# AuxHalfH.net
KiCad netlist of a schematic drawn in Altium Designer
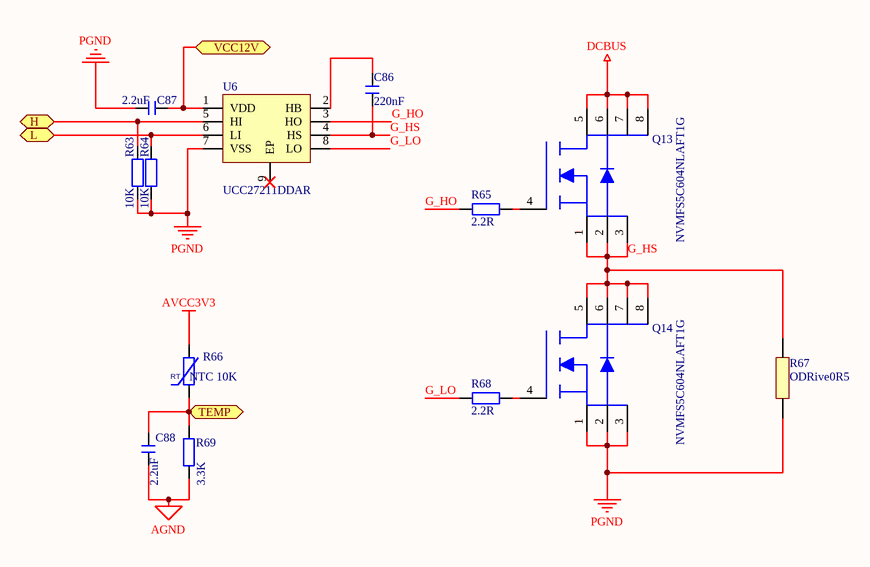
[diagram p0: AuxHalfH.SchDoc]

(export (version "E")
  (design (tool "Eeschema 10.0.6"))
  (components
    (comp (ref "C86")
      (value "220nF")
      (footprint "C 0805_L")
      (description "贴片电容")
      (libsource (lib "0.1 - 电阻-电容-电感") (part "C"))
    )
    (comp (ref "C87")
      (value "2.2uF")
      (footprint "C 0603_L")
      (description "贴片电容")
      (libsource (lib "0.1 - 电阻-电容-电感") (part "C"))
    )
    (comp (ref "C88")
      (value "2.2uF")
      (footprint "C 0603_L")
      (description "贴片电容")
      (libsource (lib "0.1 - 电阻-电容-电感") (part "C"))
    )
    (comp (ref "Q13")
      (value "NVMFS5C604NLAFT1G")
      (footprint "PG-TDSON-8_L5.0-W6.0-P1.27-LS6.2-BL-EP")
      (libsource (lib "mx_pcb_library") (part "BSC037N08NS5ATMA1"))
    )
    (comp (ref "Q14")
      (value "NVMFS5C604NLAFT1G")
      (footprint "PG-TDSON-8_L5.0-W6.0-P1.27-LS6.2-BL-EP")
      (libsource (lib "mx_pcb_library") (part "BSC037N08NS5ATMA1"))
    )
    (comp (ref "R63")
      (value "10K")
      (footprint "R 0603_L")
      (description "贴片电阻")
      (libsource (lib "0.1 - 电阻-电容-电感") (part "R"))
    )
    (comp (ref "R64")
      (value "10K")
      (footprint "R 0603_L")
      (description "贴片电阻")
      (libsource (lib "0.1 - 电阻-电容-电感") (part "R"))
    )
    (comp (ref "R65")
      (value "2.2R")
      (footprint "R 0603_L")
      (description "贴片电阻")
      (libsource (lib "0.1 - 电阻-电容-电感") (part "R"))
    )
    (comp (ref "R66")
      (value "NTC 10K")
      (footprint "R 0805-HP_L")
      (description "热敏电阻")
      (libsource (lib "0.1 - 电阻-电容-电感") (part "RT"))
    )
    (comp (ref "R67")
      (value "ODRive0R5")
      (footprint "ODrive_0R5")
      (libsource (lib "mx_pcb_library") (part "ODRive0R5"))
    )
    (comp (ref "R68")
      (value "2.2R")
      (footprint "R 0603_L")
      (description "贴片电阻")
      (libsource (lib "0.1 - 电阻-电容-电感") (part "R"))
    )
    (comp (ref "R69")
      (value "3.3K")
      (footprint "R 0805_L")
      (description "贴片电阻")
      (libsource (lib "0.1 - 电阻-电容-电感") (part "R"))
    )
    (comp (ref "U6")
      (value "UCC27211DDAR")
      (footprint "SO-8_EP")
      (libsource (lib "mx_pcb_library") (part "UCC27211DDAR"))
    )
  )
  (nets
    (net (code "1") (name "/G_HO") (class "Default")
      (node (ref "R65") (pin "1") (pinfunction "1_1") (pintype "passive"))
      (node (ref "U6") (pin "3") (pinfunction "HO_3") (pintype "passive"))
    )
    (net (code "2") (name "/G_HS") (class "Default")
      (node (ref "C86") (pin "1") (pinfunction "1_1") (pintype "passive"))
      (node (ref "Q13") (pin "1") (pinfunction "1_1") (pintype "passive"))
      (node (ref "Q13") (pin "2") (pinfunction "2_2") (pintype "passive"))
      (node (ref "Q13") (pin "3") (pinfunction "3_3") (pintype "passive"))
      (node (ref "Q14") (pin "5") (pinfunction "5_5") (pintype "passive"))
      (node (ref "Q14") (pin "6") (pinfunction "6_6") (pintype "passive"))
      (node (ref "Q14") (pin "7") (pinfunction "7_7") (pintype "passive"))
      (node (ref "Q14") (pin "8") (pinfunction "8_8") (pintype "passive"))
      (node (ref "R67") (pin "2") (pinfunction "2_2") (pintype "passive"))
      (node (ref "U6") (pin "4") (pinfunction "HS_4") (pintype "passive"))
    )
    (net (code "3") (name "/G_LO") (class "Default")
      (node (ref "R68") (pin "1") (pinfunction "1_1") (pintype "passive"))
      (node (ref "U6") (pin "8") (pinfunction "LO_8") (pintype "passive"))
    )
    (net (code "4") (name "/H") (class "Default")
      (node (ref "R63") (pin "2") (pinfunction "2_2") (pintype "passive"))
      (node (ref "U6") (pin "5") (pinfunction "HI_5") (pintype "passive"))
    )
    (net (code "5") (name "/L") (class "Default")
      (node (ref "R64") (pin "2") (pinfunction "2_2") (pintype "passive"))
      (node (ref "U6") (pin "6") (pinfunction "LI_6") (pintype "passive"))
    )
    (net (code "6") (name "/TEMP") (class "Default")
      (node (ref "C88") (pin "1") (pinfunction "1_1") (pintype "passive"))
      (node (ref "R66") (pin "1") (pinfunction "1_1") (pintype "passive"))
      (node (ref "R69") (pin "2") (pinfunction "2_2") (pintype "passive"))
    )
    (net (code "7") (name "/VCC12V") (class "Default")
      (node (ref "C87") (pin "1") (pinfunction "1_1") (pintype "passive"))
      (node (ref "U6") (pin "1") (pinfunction "VDD_1") (pintype "passive"))
    )
    (net (code "8") (name "AGND") (class "Default")
      (node (ref "C88") (pin "2") (pinfunction "2_2") (pintype "passive"))
      (node (ref "R69") (pin "1") (pinfunction "1_1") (pintype "passive"))
    )
    (net (code "9") (name "AVCC3V3") (class "Default")
      (node (ref "R66") (pin "2") (pinfunction "2_2") (pintype "passive"))
    )
    (net (code "10") (name "DCBUS") (class "Default")
      (node (ref "Q13") (pin "5") (pinfunction "5_5") (pintype "passive"))
      (node (ref "Q13") (pin "6") (pinfunction "6_6") (pintype "passive"))
      (node (ref "Q13") (pin "7") (pinfunction "7_7") (pintype "passive"))
      (node (ref "Q13") (pin "8") (pinfunction "8_8") (pintype "passive"))
    )
    (net (code "11") (name "Net-(Q13-Pad4)") (class "Default")
      (node (ref "Q13") (pin "4") (pinfunction "4_4") (pintype "passive"))
      (node (ref "R65") (pin "2") (pinfunction "2_2") (pintype "passive"))
    )
    (net (code "12") (name "Net-(Q14-Pad4)") (class "Default")
      (node (ref "Q14") (pin "4") (pinfunction "4_4") (pintype "passive"))
      (node (ref "R68") (pin "2") (pinfunction "2_2") (pintype "passive"))
    )
    (net (code "13") (name "Net-(U6-HB)") (class "Default")
      (node (ref "C86") (pin "2") (pinfunction "2_2") (pintype "passive"))
      (node (ref "U6") (pin "2") (pinfunction "HB_2") (pintype "passive"))
    )
    (net (code "14") (name "PGND") (class "Default")
      (node (ref "C87") (pin "2") (pinfunction "2_2") (pintype "passive"))
      (node (ref "Q14") (pin "1") (pinfunction "1_1") (pintype "passive"))
      (node (ref "Q14") (pin "2") (pinfunction "2_2") (pintype "passive"))
      (node (ref "Q14") (pin "3") (pinfunction "3_3") (pintype "passive"))
      (node (ref "R63") (pin "1") (pinfunction "1_1") (pintype "passive"))
      (node (ref "R64") (pin "1") (pinfunction "1_1") (pintype "passive"))
      (node (ref "R67") (pin "1") (pinfunction "1_1") (pintype "passive"))
      (node (ref "U6") (pin "7") (pinfunction "VSS_7") (pintype "passive"))
    )
    (net (code "15") (name "unconnected-(U6-EP-Pad9)") (class "Default")
      (node (ref "U6") (pin "9") (pinfunction "EP_9") (pintype "passive+no_connect"))
    )
  )
)
